# M.net
KiCad netlist of a schematic drawn in Altium Designer
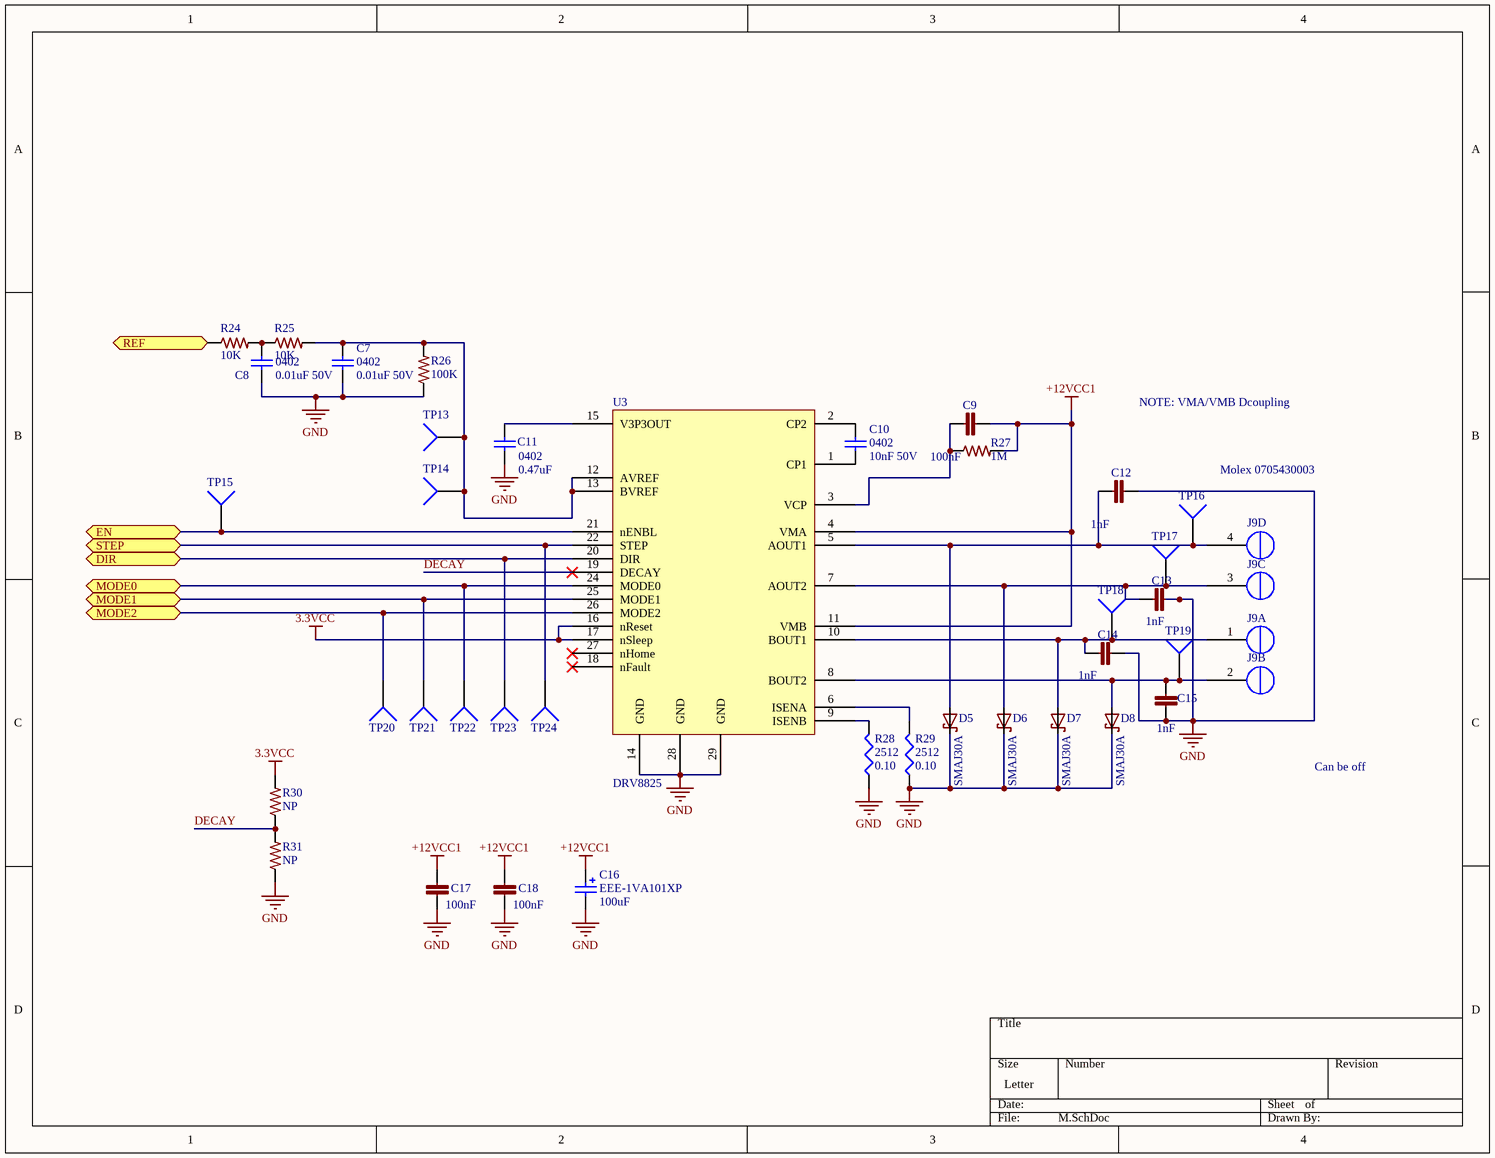
[diagram p0: M.SchDoc]

(export (version "E")
  (design (tool "Eeschema 10.0.6"))
  (components
    (comp (ref "C7")
      (value "0.01uF 50V")
      (footprint "C0402")
      (description "CAP CER 10000PF 50V X7R 0402")
      (fields
        (field (name "MFR PART #") "GRM155R71H103JA88D")
        (field (name "MFR") "Murata")
        (field (name "PACKAGEREFERENCE") "0402")
        (field (name "PUBLISHER") "Ultimachine")
      )
      (libsource (lib "Tigershark3D") (part "GRM155R71H103JA88D"))
    )
    (comp (ref "C8")
      (value "0.01uF 50V")
      (footprint "C0402")
      (description "CAP CER 10000PF 50V X7R 0402")
      (fields
        (field (name "MFR PART #") "GRM155R71H103JA88D")
        (field (name "MFR") "Murata")
        (field (name "PACKAGEREFERENCE") "0402")
        (field (name "PUBLISHER") "Ultimachine")
      )
      (libsource (lib "Tigershark3D") (part "GRM155R71H103JA88D"))
    )
    (comp (ref "C9")
      (value "100nF")
      (footprint "C0402")
      (description "CAP CER 0402 100nF 16V 10% X7R")
      (fields
        (field (name "MANUFACTURERPARTNUMBER") "GRM155R71C104KA88D")
        (field (name "PUBLISHER") "UltiMachine")
      )
      (libsource (lib "3Delight") (part "GRM155R71C104KA88D"))
    )
    (comp (ref "C10")
      (value "10nF 50V")
      (footprint "C0402")
      (description "CAP CER 10nF 50V X7R 0402")
      (fields
        (field (name "MFR PART #") "GRM155R71H103JA88D")
        (field (name "MFR") "Murata")
        (field (name "PACKAGEREFERENCE") "0402")
        (field (name "PUBLISHER") "Ultimachine")
      )
      (libsource (lib "Tigershark3D") (part "GRM155R71H103JA88D"))
    )
    (comp (ref "C11")
      (value "0.47uF")
      (footprint "3Delight:C0402")
      (description "0.47uF 6.3v C0402 - GRM155R60J474KE19D")
      (fields
        (field (name "MFR PART #") "GRM155R60J474KE19D")
        (field (name "MFR") "Murata")
        (field (name "PACKAGEREFERENCE") "0402")
        (field (name "PUBLISHER") "Ultimachine")
      )
      (libsource (lib "Tigershark3D") (part "GRM155R60J474KE19D"))
    )
    (comp (ref "C12")
      (value "1nF")
      (footprint "C0603")
      (description "CAP CER 0603  1nF 50v 10% X7R")
      (fields
        (field (name "MANUFACTURERPARTNUMBER") "C0603C102K5RACTU")
        (field (name "PUBLISHER") "UltiMachine")
      )
      (libsource (lib "3Delight") (part "C0603C102K5RACTU"))
    )
    (comp (ref "C13")
      (value "1nF")
      (footprint "C0603")
      (description "CAP CER 0603  1nF 50v 10% X7R")
      (fields
        (field (name "MANUFACTURERPARTNUMBER") "C0603C102K5RACTU")
        (field (name "PUBLISHER") "UltiMachine")
      )
      (libsource (lib "3Delight") (part "C0603C102K5RACTU"))
    )
    (comp (ref "C14")
      (value "1nF")
      (footprint "C0603")
      (description "CAP CER 0603  1nF 50v 10% X7R")
      (fields
        (field (name "MANUFACTURERPARTNUMBER") "C0603C102K5RACTU")
        (field (name "PUBLISHER") "UltiMachine")
      )
      (libsource (lib "3Delight") (part "C0603C102K5RACTU"))
    )
    (comp (ref "C15")
      (value "1nF")
      (footprint "C0603")
      (description "CAP CER 0603  1nF 50v 10% X7R")
      (fields
        (field (name "MANUFACTURERPARTNUMBER") "C0603C102K5RACTU")
        (field (name "PUBLISHER") "UltiMachine")
      )
      (libsource (lib "") (part "C0603C102K5RACTU_1"))
    )
    (comp (ref "C16")
      (value "EEE-1VA101XP")
      (footprint "EEE-1VA101XP")
      (description "CAP ALUM 100UF 35V 20% SMD")
      (fields (field (name "DIGIKEY PART #") "PCE3951CT-ND") (field (name "ALTIUM_VALUE") "100uF"))
      (libsource (lib "Tigershark3D") (part "EEE-1VA101XP"))
    )
    (comp (ref "C17")
      (value "100nF")
      (footprint "C0603")
      (description "CAP CER 0603 100nF 50V 10% X7R")
      (fields
        (field (name "MANUFACTURERPARTNUMBER") "C0603C104K5RACTU")
        (field (name "PUBLISHER") "UltiMachine")
      )
      (libsource (lib "3Delight") (part "C0603C104K5RACTU"))
    )
    (comp (ref "C18")
      (value "100nF")
      (footprint "C0603")
      (description "CAP CER 0603 100nF 50V 10% X7R")
      (fields
        (field (name "MANUFACTURERPARTNUMBER") "C0603C104K5RACTU")
        (field (name "PUBLISHER") "UltiMachine")
      )
      (libsource (lib "3Delight") (part "C0603C104K5RACTU"))
    )
    (comp (ref "D5")
      (value "SMAJ30A")
      (footprint "SMA-SM")
      (description "DIODE TVS 30V SMA")
      (fields (field (name "PUBLISHER") "UltiMachine"))
      (libsource (lib "3Delight") (part "SMAJ30A"))
    )
    (comp (ref "D6")
      (value "SMAJ30A")
      (footprint "SMA-SM")
      (description "DIODE TVS 30V SMA")
      (fields (field (name "PUBLISHER") "UltiMachine"))
      (libsource (lib "3Delight") (part "SMAJ30A"))
    )
    (comp (ref "D7")
      (value "SMAJ30A")
      (footprint "SMA-SM")
      (description "DIODE TVS 30V SMA")
      (fields (field (name "PUBLISHER") "UltiMachine"))
      (libsource (lib "3Delight") (part "SMAJ30A"))
    )
    (comp (ref "D8")
      (value "SMAJ30A")
      (footprint "SMA-SM")
      (description "DIODE TVS 30V SMA")
      (fields (field (name "PUBLISHER") "UltiMachine"))
      (libsource (lib "3Delight") (part "SMAJ30A"))
    )
    (comp (ref "J9")
      (value "Molex 0705430003")
      (footprint "4POL254")
      (description "Molex 4 Pin Clip Connector")
      (libsource (lib "ZMBo Schematic Library") (part "Molex 0705430003 Alt"))
    )
    (comp (ref "R24")
      (value "10K")
      (footprint "R0402")
      (description "RES SMD 10K OHM 1% 1/16W 0402")
      (fields
        (field (name "MANUFACTURERPARTNUMBER") "RC0402FR-0710KP")
        (field (name "PUBLISHER") "UltiMachine")
      )
      (libsource (lib "3Delight") (part "RC0402FR-0710KP"))
    )
    (comp (ref "R25")
      (value "10K")
      (footprint "R0402")
      (description "RES SMD 10K OHM 1% 1/16W 0402")
      (fields
        (field (name "MANUFACTURERPARTNUMBER") "RC0402FR-0710KP")
        (field (name "PUBLISHER") "UltiMachine")
      )
      (libsource (lib "3Delight") (part "RC0402FR-0710KP"))
    )
    (comp (ref "R26")
      (value "100K")
      (footprint "R0402")
      (description "RES SMD 100K OHM 1% 1/16W 0402")
      (fields
        (field (name "MANUFACTURER") "Samsung")
        (field (name "MANUFACTURERPARTNUMBER") "RC1005F104CS")
        (field (name "PUBLISHER") "UltiMachine")
      )
      (libsource (lib "Tigershark3D") (part "RC1005F104CS"))
    )
    (comp (ref "R27")
      (value "1M")
      (footprint "3Delight:R0402")
      (description "RES 0402 1M 100mW 5%")
      (fields (field (name "MANUFACTURERPARTNUMBER") "ERJ2GEJ105X") (field (name "PUBLISHER") "UltiMachine"))
      (libsource (lib "Tigershark3D") (part "ERJ2GEJ105X"))
    )
    (comp (ref "R28")
      (value "2512")
      (footprint "2512R-0.55")
      (description "RES SMD 0.1 OHM 1% 2W 2512")
      (fields (field (name "MFR") "Stackpole ELectronics Inc") (field (name "ALTIUM_VALUE") "0.10"))
      (libsource (lib "Tigershark3D") (part "CSRN2512FTR100"))
    )
    (comp (ref "R29")
      (value "2512")
      (footprint "2512R-0.55")
      (description "RES SMD 0.1 OHM 1% 2W 2512")
      (fields (field (name "MFR") "Stackpole ELectronics Inc") (field (name "ALTIUM_VALUE") "0.10"))
      (libsource (lib "Tigershark3D") (part "CSRN2512FTR100"))
    )
    (comp (ref "R30")
      (value "NP")
      (footprint "R0402")
      (description "Resistor")
      (fields (field (name "PUBLISHER") "UltiMachine"))
      (libsource (lib "3Delight") (part "Resistor"))
    )
    (comp (ref "R31")
      (value "NP")
      (footprint "R0402")
      (description "Resistor")
      (fields (field (name "PUBLISHER") "UltiMachine"))
      (libsource (lib "3Delight") (part "Resistor"))
    )
    (comp (ref "TP13")
      (value "TP4")
      (footprint "TP-2")
      (description "Socket")
      (fields (field (name "PUBLISHER") "Altium Limited"))
      (libsource (lib "ZMBo Schematic Library") (part "Socket"))
    )
    (comp (ref "TP14")
      (value "TP4")
      (footprint "TP-2")
      (description "Socket")
      (fields (field (name "PUBLISHER") "Altium Limited"))
      (libsource (lib "ZMBo Schematic Library") (part "Socket"))
    )
    (comp (ref "TP15")
      (value "TP4")
      (footprint "TP-2")
      (description "Socket")
      (fields (field (name "PUBLISHER") "Altium Limited"))
      (libsource (lib "ZMBo Schematic Library") (part "Socket"))
    )
    (comp (ref "TP16")
      (value "TP4")
      (footprint "TP-2")
      (description "Socket")
      (fields (field (name "PUBLISHER") "Altium Limited"))
      (libsource (lib "ZMBo Schematic Library") (part "Socket"))
    )
    (comp (ref "TP17")
      (value "TP4")
      (footprint "TP-2")
      (description "Socket")
      (fields (field (name "PUBLISHER") "Altium Limited"))
      (libsource (lib "ZMBo Schematic Library") (part "Socket"))
    )
    (comp (ref "TP18")
      (value "TP4")
      (footprint "TP-2")
      (description "Socket")
      (fields (field (name "PUBLISHER") "Altium Limited"))
      (libsource (lib "ZMBo Schematic Library") (part "Socket"))
    )
    (comp (ref "TP19")
      (value "TP4")
      (footprint "TP-2")
      (description "Socket")
      (fields (field (name "PUBLISHER") "Altium Limited"))
      (libsource (lib "ZMBo Schematic Library") (part "Socket"))
    )
    (comp (ref "TP20")
      (value "TP4")
      (footprint "TP-2")
      (description "Socket")
      (fields (field (name "PUBLISHER") "Altium Limited"))
      (libsource (lib "ZMBo Schematic Library") (part "Socket"))
    )
    (comp (ref "TP21")
      (value "TP4")
      (footprint "TP-2")
      (description "Socket")
      (fields (field (name "PUBLISHER") "Altium Limited"))
      (libsource (lib "ZMBo Schematic Library") (part "Socket"))
    )
    (comp (ref "TP22")
      (value "TP4")
      (footprint "TP-2")
      (description "Socket")
      (fields (field (name "PUBLISHER") "Altium Limited"))
      (libsource (lib "ZMBo Schematic Library") (part "Socket"))
    )
    (comp (ref "TP23")
      (value "TP4")
      (footprint "TP-2")
      (description "Socket")
      (fields (field (name "PUBLISHER") "Altium Limited"))
      (libsource (lib "ZMBo Schematic Library") (part "Socket"))
    )
    (comp (ref "TP24")
      (value "TP4")
      (footprint "TP-2")
      (description "Socket")
      (fields (field (name "PUBLISHER") "Altium Limited"))
      (libsource (lib "ZMBo Schematic Library") (part "Socket"))
    )
    (comp (ref "U3")
      (value "DRV8825")
      (footprint "DRV8825PWPR")
      (description "DRV8825 Ti Stepper Driver")
      (fields (field (name "PART NUMBER") "DRV8825PWPR") (field (name "VOLTAGE") "8.2-45VDC"))
      (libsource (lib "Tigershark3D") (part "DRV8825"))
    )
  )
  (nets
    (net (code "1") (name "+12VCC1") (class "Default")
      (node (ref "C16") (pin "1") (pinfunction "1_1") (pintype "passive"))
      (node (ref "C17") (pin "1") (pinfunction "1_1") (pintype "passive"))
      (node (ref "C18") (pin "1") (pinfunction "1_1") (pintype "passive"))
      (node (ref "C9") (pin "2") (pinfunction "2_2") (pintype "passive"))
      (node (ref "R27") (pin "2") (pinfunction "2_2") (pintype "passive"))
      (node (ref "U3") (pin "11") (pinfunction "VMB_11") (pintype "passive"))
      (node (ref "U3") (pin "4") (pinfunction "VMA_4") (pintype "passive"))
    )
    (net (code "2") (name "/DECAY") (class "Default")
      (node (ref "R30") (pin "1") (pinfunction "1_1") (pintype "passive"))
      (node (ref "R31") (pin "2") (pinfunction "2_2") (pintype "passive"))
      (node (ref "U3") (pin "19") (pinfunction "DECAY_19") (pintype "passive"))
    )
    (net (code "3") (name "/DIR") (class "Default")
      (node (ref "TP23") (pin "1") (pinfunction "1_1") (pintype "passive"))
      (node (ref "U3") (pin "20") (pinfunction "DIR_20") (pintype "passive"))
    )
    (net (code "4") (name "/EN") (class "Default")
      (node (ref "TP15") (pin "1") (pinfunction "1_1") (pintype "passive"))
      (node (ref "U3") (pin "21") (pinfunction "nENBL_21") (pintype "passive"))
    )
    (net (code "5") (name "/MODE0") (class "Default")
      (node (ref "TP22") (pin "1") (pinfunction "1_1") (pintype "passive"))
      (node (ref "U3") (pin "24") (pinfunction "MODE0_24") (pintype "passive"))
    )
    (net (code "6") (name "/MODE1") (class "Default")
      (node (ref "TP21") (pin "1") (pinfunction "1_1") (pintype "passive"))
      (node (ref "U3") (pin "25") (pinfunction "MODE1_25") (pintype "passive"))
    )
    (net (code "7") (name "/MODE2") (class "Default")
      (node (ref "TP20") (pin "1") (pinfunction "1_1") (pintype "passive"))
      (node (ref "U3") (pin "26") (pinfunction "MODE2_26") (pintype "passive"))
    )
    (net (code "8") (name "/REF") (class "Default")
      (node (ref "R24") (pin "1") (pinfunction "1_1") (pintype "passive"))
    )
    (net (code "9") (name "/STEP") (class "Default")
      (node (ref "TP24") (pin "1") (pinfunction "1_1") (pintype "passive"))
      (node (ref "U3") (pin "22") (pinfunction "STEP_22") (pintype "passive"))
    )
    (net (code "10") (name "3.3VCC") (class "Default")
      (node (ref "R30") (pin "2") (pinfunction "2_2") (pintype "passive"))
      (node (ref "U3") (pin "16") (pinfunction "nReset_16") (pintype "passive"))
      (node (ref "U3") (pin "17") (pinfunction "nSleep_17") (pintype "passive"))
    )
    (net (code "11") (name "GND") (class "Default")
      (node (ref "C11") (pin "1") (pinfunction "1_1") (pintype "passive"))
      (node (ref "C12") (pin "2") (pinfunction "2_2") (pintype "passive"))
      (node (ref "C13") (pin "2") (pinfunction "2_2") (pintype "passive"))
      (node (ref "C14") (pin "2") (pinfunction "2_2") (pintype "passive"))
      (node (ref "C15") (pin "1") (pinfunction "1_1") (pintype "passive"))
      (node (ref "C16") (pin "2") (pinfunction "2_2") (pintype "passive"))
      (node (ref "C17") (pin "2") (pinfunction "2_2") (pintype "passive"))
      (node (ref "C18") (pin "2") (pinfunction "2_2") (pintype "passive"))
      (node (ref "C7") (pin "1") (pinfunction "1_1") (pintype "passive"))
      (node (ref "C8") (pin "1") (pinfunction "1_1") (pintype "passive"))
      (node (ref "D5") (pin "C") (pinfunction "C_C") (pintype "passive"))
      (node (ref "D6") (pin "C") (pinfunction "C_C") (pintype "passive"))
      (node (ref "D7") (pin "C") (pinfunction "C_C") (pintype "passive"))
      (node (ref "D8") (pin "C") (pinfunction "C_C") (pintype "passive"))
      (node (ref "R26") (pin "1") (pinfunction "1_1") (pintype "passive"))
      (node (ref "R28") (pin "1") (pinfunction "1_1") (pintype "passive"))
      (node (ref "R29") (pin "1") (pinfunction "1_1") (pintype "passive"))
      (node (ref "R31") (pin "1") (pinfunction "1_1") (pintype "passive"))
      (node (ref "U3") (pin "14") (pinfunction "GND_14") (pintype "passive"))
      (node (ref "U3") (pin "28") (pinfunction "GND_28") (pintype "passive"))
      (node (ref "U3") (pin "29") (pinfunction "GND_29") (pintype "passive"))
    )
    (net (code "12") (name "Net-(C8-Pad2)") (class "Default")
      (node (ref "C8") (pin "2") (pinfunction "2_2") (pintype "passive"))
      (node (ref "R24") (pin "2") (pinfunction "2_2") (pintype "passive"))
      (node (ref "R25") (pin "1") (pinfunction "1_1") (pintype "passive"))
    )
    (net (code "13") (name "Net-(J9A-OUT2B)") (class "Default")
      (node (ref "C14") (pin "1") (pinfunction "1_1") (pintype "passive"))
      (node (ref "D7") (pin "A") (pinfunction "A_A") (pintype "passive"))
      (node (ref "J9") (pin "1") (pinfunction "OUT2B_1") (pintype "passive"))
      (node (ref "TP18") (pin "1") (pinfunction "1_1") (pintype "passive"))
      (node (ref "U3") (pin "10") (pinfunction "BOUT1_10") (pintype "passive"))
    )
    (net (code "14") (name "Net-(J9B-OUT2A)") (class "Default")
      (node (ref "C15") (pin "2") (pinfunction "2_2") (pintype "passive"))
      (node (ref "D8") (pin "A") (pinfunction "A_A") (pintype "passive"))
      (node (ref "J9") (pin "2") (pinfunction "OUT2A_2") (pintype "passive"))
      (node (ref "TP19") (pin "1") (pinfunction "1_1") (pintype "passive"))
      (node (ref "U3") (pin "8") (pinfunction "BOUT2_8") (pintype "passive"))
    )
    (net (code "15") (name "Net-(J9C-OUT1A)") (class "Default")
      (node (ref "C13") (pin "1") (pinfunction "1_1") (pintype "passive"))
      (node (ref "D6") (pin "A") (pinfunction "A_A") (pintype "passive"))
      (node (ref "J9") (pin "3") (pinfunction "OUT1A_3") (pintype "passive"))
      (node (ref "TP17") (pin "1") (pinfunction "1_1") (pintype "passive"))
      (node (ref "U3") (pin "7") (pinfunction "AOUT2_7") (pintype "passive"))
    )
    (net (code "16") (name "Net-(J9D-OUT1B)") (class "Default")
      (node (ref "C12") (pin "1") (pinfunction "1_1") (pintype "passive"))
      (node (ref "D5") (pin "A") (pinfunction "A_A") (pintype "passive"))
      (node (ref "J9") (pin "4") (pinfunction "OUT1B_4") (pintype "passive"))
      (node (ref "TP16") (pin "1") (pinfunction "1_1") (pintype "passive"))
      (node (ref "U3") (pin "5") (pinfunction "AOUT1_5") (pintype "passive"))
    )
    (net (code "17") (name "Net-(U3-AVREF)") (class "Default")
      (node (ref "C7") (pin "2") (pinfunction "2_2") (pintype "passive"))
      (node (ref "R25") (pin "2") (pinfunction "2_2") (pintype "passive"))
      (node (ref "R26") (pin "2") (pinfunction "2_2") (pintype "passive"))
      (node (ref "TP13") (pin "1") (pinfunction "1_1") (pintype "passive"))
      (node (ref "TP14") (pin "1") (pinfunction "1_1") (pintype "passive"))
      (node (ref "U3") (pin "12") (pinfunction "AVREF_12") (pintype "passive"))
      (node (ref "U3") (pin "13") (pinfunction "BVREF_13") (pintype "passive"))
    )
    (net (code "18") (name "Net-(U3-CP1)") (class "Default")
      (node (ref "C10") (pin "1") (pinfunction "1_1") (pintype "passive"))
      (node (ref "U3") (pin "1") (pinfunction "CP1_1") (pintype "passive"))
    )
    (net (code "19") (name "Net-(U3-CP2)") (class "Default")
      (node (ref "C10") (pin "2") (pinfunction "2_2") (pintype "passive"))
      (node (ref "U3") (pin "2") (pinfunction "CP2_2") (pintype "passive"))
    )
    (net (code "20") (name "Net-(U3-ISENA)") (class "Default")
      (node (ref "R29") (pin "2") (pinfunction "2_2") (pintype "passive"))
      (node (ref "U3") (pin "6") (pinfunction "ISENA_6") (pintype "passive"))
    )
    (net (code "21") (name "Net-(U3-ISENB)") (class "Default")
      (node (ref "R28") (pin "2") (pinfunction "2_2") (pintype "passive"))
      (node (ref "U3") (pin "9") (pinfunction "ISENB_9") (pintype "passive"))
    )
    (net (code "22") (name "Net-(U3-V3P3OUT)") (class "Default")
      (node (ref "C11") (pin "2") (pinfunction "2_2") (pintype "passive"))
      (node (ref "U3") (pin "15") (pinfunction "V3P3OUT_15") (pintype "passive"))
    )
    (net (code "23") (name "Net-(U3-VCP)") (class "Default")
      (node (ref "C9") (pin "1") (pinfunction "1_1") (pintype "passive"))
      (node (ref "R27") (pin "1") (pinfunction "1_1") (pintype "passive"))
      (node (ref "U3") (pin "3") (pinfunction "VCP_3") (pintype "passive"))
    )
    (net (code "24") (name "unconnected-(U3-NC-Pad23)") (class "Default")
      (node (ref "U3") (pin "23") (pinfunction "NC_23") (pintype "passive"))
    )
    (net (code "25") (name "unconnected-(U3-nFault-Pad18)") (class "Default")
      (node (ref "U3") (pin "18") (pinfunction "nFault_18") (pintype "passive+no_connect"))
    )
    (net (code "26") (name "unconnected-(U3-nHome-Pad27)") (class "Default")
      (node (ref "U3") (pin "27") (pinfunction "nHome_27") (pintype "passive+no_connect"))
    )
  )
)
